# SC20.net
KiCad netlist of a schematic drawn in Altium Designer
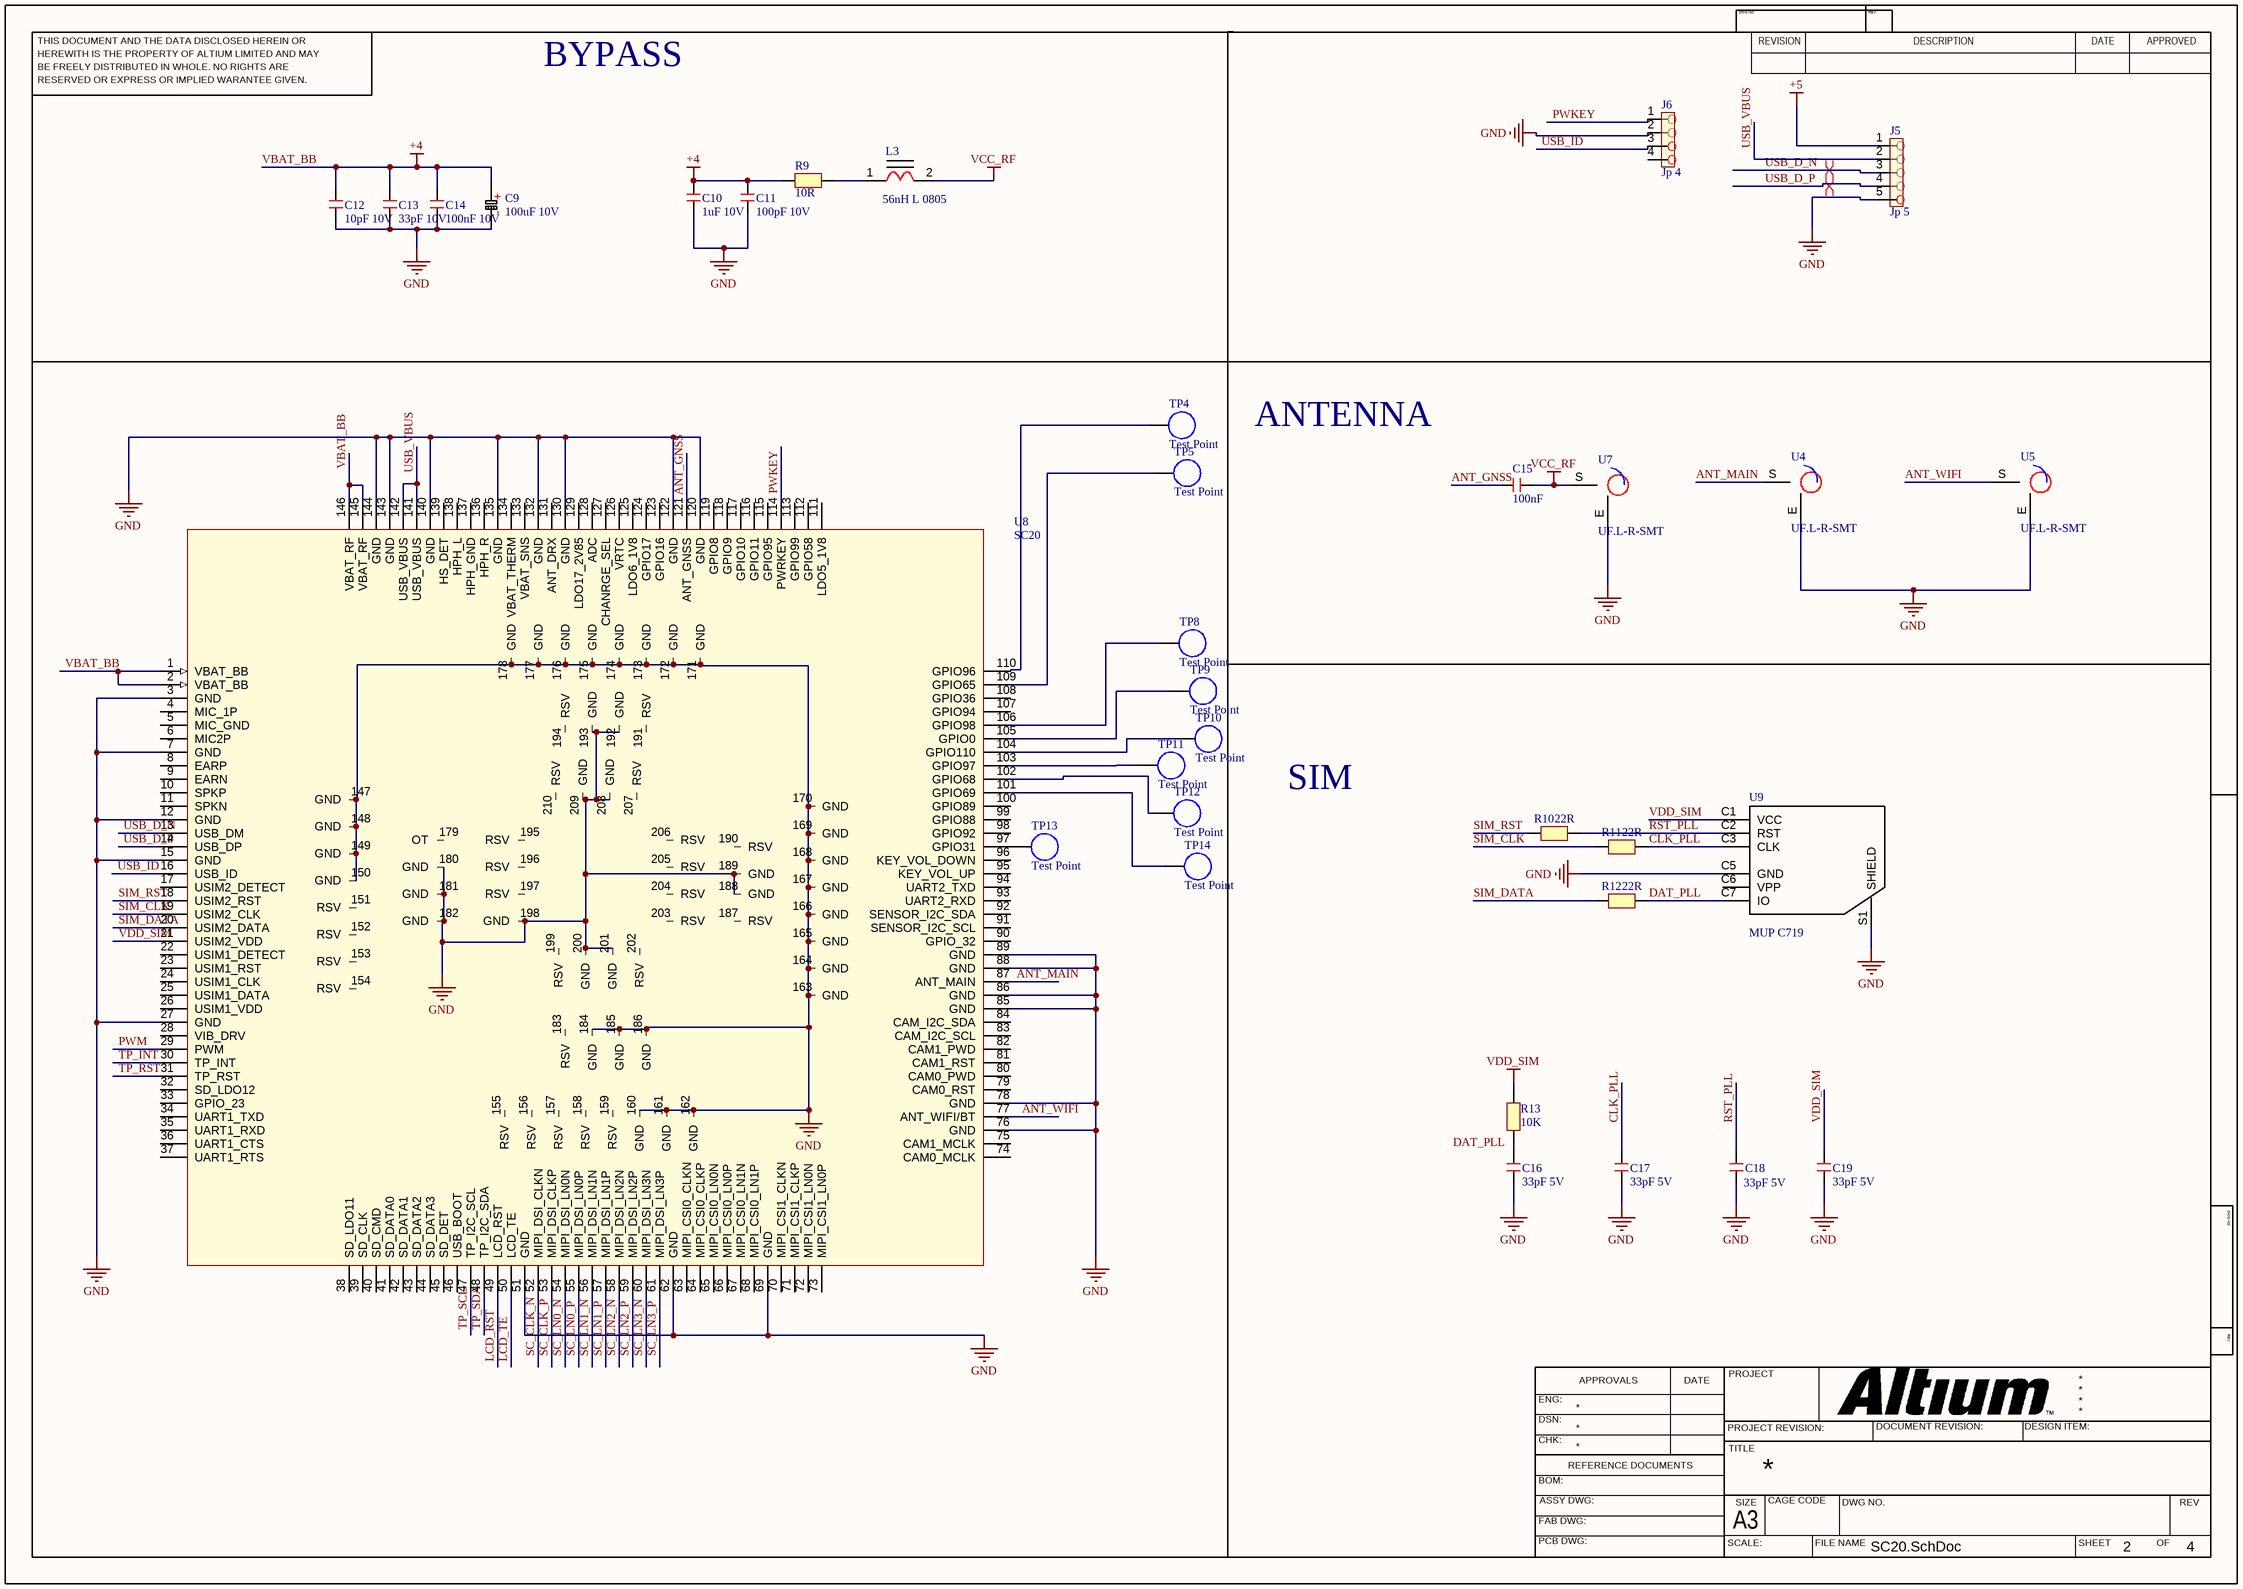
[diagram p0: SC20.SchDoc]

(export (version "E")
  (design (tool "Eeschema 10.0.6"))
  (components
    (comp (ref "C9")
      (value "100uF 10V")
      (footprint "CAPACITOR TALTALIUM 7443")
      (libsource (lib "NAVISTAR") (part "C Polarize 8x10.2"))
    )
    (comp (ref "C10") (value "1uF 10V") (footprint "C 0805") (libsource (lib "MAX2769_GPS") (part "C 0805")))
    (comp (ref "C11")
      (value "100pF 10V")
      (footprint "C 0805")
      (libsource (lib "MAX2769_GPS") (part "C 0805"))
    )
    (comp (ref "C12") (value "10pF 10V") (footprint "C 0805") (libsource (lib "MAX2769_GPS") (part "C 0805")))
    (comp (ref "C13") (value "33pF 10V") (footprint "C 0805") (libsource (lib "MAX2769_GPS") (part "C 0805")))
    (comp (ref "C14")
      (value "100nF 10V")
      (footprint "C 0805")
      (libsource (lib "MAX2769_GPS") (part "C 0805"))
    )
    (comp (ref "C15") (value "100nF") (footprint "C 0805") (libsource (lib "MAX2769_GPS") (part "C 0805")))
    (comp (ref "C16") (value "33pF 5V") (footprint "C 0805") (libsource (lib "MAX2769_GPS") (part "C 0805")))
    (comp (ref "C17") (value "33pF 5V") (footprint "C 0805") (libsource (lib "MAX2769_GPS") (part "C 0805")))
    (comp (ref "C18") (value "33pF 5V") (footprint "C 0805") (libsource (lib "MAX2769_GPS") (part "C 0805")))
    (comp (ref "C19") (value "33pF 5V") (footprint "C 0805") (libsource (lib "MAX2769_GPS") (part "C 0805")))
    (comp (ref "J5") (value "Jp 5") (footprint "Jp5") (libsource (lib "NAVISTAR") (part "Jp 5")))
    (comp (ref "J6") (value "Jp 4") (footprint "Jp4") (libsource (lib "NAVISTAR") (part "Jp 4")))
    (comp (ref "L3")
      (value "56nH L 0805")
      (footprint "Ferrite 0805")
      (libsource (lib "NAVISTAR") (part "Ferite 0805"))
    )
    (comp (ref "R9") (value "10R") (footprint "R 0805") (libsource (lib "") (part "R 0805_1")))
    (comp (ref "R10") (value "22R") (footprint "R 0805") (libsource (lib "") (part "R 0805_2")))
    (comp (ref "R11") (value "22R") (footprint "R 0805") (libsource (lib "") (part "R 0805_2")))
    (comp (ref "R12") (value "22R") (footprint "R 0805") (libsource (lib "") (part "R 0805_2")))
    (comp (ref "R13") (value "10K") (footprint "R 0805") (libsource (lib "MAX2769_GPS") (part "R 0805")))
    (comp (ref "TP4")
      (value "Test Point")
      (footprint "Test Point")
      (libsource (lib "NAVISTAR") (part "Test Point"))
    )
    (comp (ref "TP5")
      (value "Test Point")
      (footprint "Test Point")
      (libsource (lib "NAVISTAR") (part "Test Point"))
    )
    (comp (ref "TP8")
      (value "Test Point")
      (footprint "Test Point")
      (libsource (lib "NAVISTAR") (part "Test Point"))
    )
    (comp (ref "TP9")
      (value "Test Point")
      (footprint "Test Point")
      (libsource (lib "NAVISTAR") (part "Test Point"))
    )
    (comp (ref "TP10")
      (value "Test Point")
      (footprint "Test Point")
      (libsource (lib "NAVISTAR") (part "Test Point"))
    )
    (comp (ref "TP11")
      (value "Test Point")
      (footprint "Test Point")
      (libsource (lib "NAVISTAR") (part "Test Point"))
    )
    (comp (ref "TP12")
      (value "Test Point")
      (footprint "Test Point")
      (libsource (lib "NAVISTAR") (part "Test Point"))
    )
    (comp (ref "TP13")
      (value "Test Point")
      (footprint "Test Point")
      (libsource (lib "NAVISTAR") (part "Test Point"))
    )
    (comp (ref "TP14")
      (value "Test Point")
      (footprint "Test Point")
      (libsource (lib "NAVISTAR") (part "Test Point"))
    )
    (comp (ref "U4")
      (value "UF.L-R-SMT")
      (footprint "UFL")
      (libsource (lib "NAVISTAR_SoC") (part "UF.L-R-SMT"))
    )
    (comp (ref "U5")
      (value "UF.L-R-SMT")
      (footprint "UFL")
      (libsource (lib "NAVISTAR_SoC") (part "UF.L-R-SMT"))
    )
    (comp (ref "U7")
      (value "UF.L-R-SMT")
      (footprint "UFL")
      (libsource (lib "NAVISTAR_SoC") (part "UF.L-R-SMT"))
    )
    (comp (ref "U8") (value "SC20") (footprint "SC20") (libsource (lib "NAVISTAR_SoC") (part "SC20")))
    (comp (ref "U9") (value "MUP C719") (footprint "MPU C719") (libsource (lib "NAVISTAR") (part "MUP C719")))
  )
  (nets
    (net (code "1") (name "+4") (class "Default")
      (node (ref "C10") (pin "2") (pintype "passive"))
      (node (ref "C11") (pin "2") (pintype "passive"))
      (node (ref "C12") (pin "2") (pintype "passive"))
      (node (ref "C13") (pin "2") (pintype "passive"))
      (node (ref "C14") (pin "2") (pintype "passive"))
      (node (ref "C9") (pin "1") (pintype "passive"))
      (node (ref "R9") (pin "2") (pintype "passive"))
      (node (ref "U8") (pin "1") (pinfunction "VBAT_BB_1") (pintype "input"))
      (node (ref "U8") (pin "145") (pinfunction "VBAT_RF_145") (pintype "passive"))
      (node (ref "U8") (pin "146") (pinfunction "VBAT_RF_146") (pintype "passive"))
      (node (ref "U8") (pin "2") (pinfunction "VBAT_BB_2") (pintype "input"))
    )
    (net (code "2") (name "+5") (class "Default") (node (ref "J5") (pin "1") (pintype "passive")))
    (net (code "3") (name "/ANT_GNSS") (class "Default")
      (node (ref "C15") (pin "2") (pintype "passive"))
      (node (ref "U8") (pin "121") (pinfunction "ANT_GNSS_121") (pintype "passive"))
    )
    (net (code "4") (name "/ANT_MAIN") (class "Default")
      (node (ref "U4") (pin "S") (pintype "passive"))
      (node (ref "U8") (pin "87") (pinfunction "ANT_MAIN_87") (pintype "passive"))
    )
    (net (code "5") (name "/ANT_WIFI") (class "Default")
      (node (ref "U5") (pin "S") (pintype "passive"))
      (node (ref "U8") (pin "77") (pinfunction "ANT_WIFI/BT_77") (pintype "passive"))
    )
    (net (code "6") (name "/CLK_PLL") (class "Default")
      (node (ref "C17") (pin "2") (pintype "passive"))
      (node (ref "R11") (pin "2") (pintype "passive"))
      (node (ref "U9") (pin "C3") (pinfunction "CLK_C3") (pintype "passive"))
    )
    (net (code "7") (name "/DAT_PLL") (class "Default")
      (node (ref "R12") (pin "2") (pintype "passive"))
      (node (ref "U9") (pin "C7") (pinfunction "IO_C7") (pintype "passive"))
    )
    (net (code "8") (name "/LCD_RST") (class "Default")
      (node (ref "U8") (pin "49") (pinfunction "LCD_RST_49") (pintype "passive"))
    )
    (net (code "9") (name "/LCD_TE") (class "Default")
      (node (ref "U8") (pin "50") (pinfunction "LCD_TE_50") (pintype "passive"))
    )
    (net (code "10") (name "/PWKEY") (class "Default")
      (node (ref "J6") (pin "1") (pintype "passive"))
      (node (ref "U8") (pin "114") (pinfunction "PWRKEY_114") (pintype "passive"))
    )
    (net (code "11") (name "/PWM") (class "Default")
      (node (ref "U8") (pin "29") (pinfunction "PWM_29") (pintype "passive"))
    )
    (net (code "12") (name "/RST_PLL") (class "Default")
      (node (ref "C18") (pin "2") (pintype "passive"))
      (node (ref "R10") (pin "2") (pintype "passive"))
      (node (ref "U9") (pin "C2") (pinfunction "RST_C2") (pintype "passive"))
    )
    (net (code "13") (name "/SC_CLK_N") (class "Default")
      (node (ref "U8") (pin "52") (pinfunction "MIPI_DSI_CLKN_52") (pintype "passive"))
    )
    (net (code "14") (name "/SC_CLK_P") (class "Default")
      (node (ref "U8") (pin "53") (pinfunction "MIPI_DSI_CLKP_53") (pintype "passive"))
    )
    (net (code "15") (name "/SC_LN0_N") (class "Default")
      (node (ref "U8") (pin "54") (pinfunction "MIPI_DSI_LN0N_54") (pintype "passive"))
    )
    (net (code "16") (name "/SC_LN0_P") (class "Default")
      (node (ref "U8") (pin "55") (pinfunction "MIPI_DSI_LN0P_55") (pintype "passive"))
    )
    (net (code "17") (name "/SC_LN1_N") (class "Default")
      (node (ref "U8") (pin "56") (pinfunction "MIPI_DSI_LN1N_56") (pintype "passive"))
    )
    (net (code "18") (name "/SC_LN1_P") (class "Default")
      (node (ref "U8") (pin "57") (pinfunction "MIPI_DSI_LN1P_57") (pintype "passive"))
    )
    (net (code "19") (name "/SC_LN2_N") (class "Default")
      (node (ref "U8") (pin "58") (pinfunction "MIPI_DSI_LN2N_58") (pintype "passive"))
    )
    (net (code "20") (name "/SC_LN2_P") (class "Default")
      (node (ref "U8") (pin "59") (pinfunction "MIPI_DSI_LN2P_59") (pintype "passive"))
    )
    (net (code "21") (name "/SC_LN3_N") (class "Default")
      (node (ref "U8") (pin "60") (pinfunction "MIPI_DSI_LN3N_60") (pintype "passive"))
    )
    (net (code "22") (name "/SC_LN3_P") (class "Default")
      (node (ref "U8") (pin "61") (pinfunction "MIPI_DSI_LN3P_61") (pintype "passive"))
    )
    (net (code "23") (name "/SIM_CLK") (class "Default")
      (node (ref "R11") (pin "1") (pintype "passive"))
      (node (ref "U8") (pin "19") (pinfunction "USIM2_CLK_19") (pintype "passive"))
    )
    (net (code "24") (name "/SIM_DATA") (class "Default")
      (node (ref "R12") (pin "1") (pintype "passive"))
      (node (ref "U8") (pin "20") (pinfunction "USIM2_DATA_20") (pintype "passive"))
    )
    (net (code "25") (name "/SIM_RST") (class "Default")
      (node (ref "R10") (pin "1") (pintype "passive"))
      (node (ref "U8") (pin "18") (pinfunction "USIM2_RST_18") (pintype "passive"))
    )
    (net (code "26") (name "/TP_INT") (class "Default")
      (node (ref "U8") (pin "30") (pinfunction "TP_INT_30") (pintype "passive"))
    )
    (net (code "27") (name "/TP_RST") (class "Default")
      (node (ref "U8") (pin "31") (pinfunction "TP_RST_31") (pintype "passive"))
    )
    (net (code "28") (name "/TP_SCL") (class "Default")
      (node (ref "U8") (pin "47") (pinfunction "TP_I2C_SCL_47") (pintype "passive"))
    )
    (net (code "29") (name "/TP_SDA") (class "Default")
      (node (ref "U8") (pin "48") (pinfunction "TP_I2C_SDA_48") (pintype "passive"))
    )
    (net (code "30") (name "/USB_D_N") (class "Default")
      (node (ref "J5") (pin "3") (pintype "passive"))
      (node (ref "U8") (pin "13") (pinfunction "USB_DM_13") (pintype "passive"))
    )
    (net (code "31") (name "/USB_D_P") (class "Default")
      (node (ref "J5") (pin "4") (pintype "passive"))
      (node (ref "U8") (pin "14") (pinfunction "USB_DP_14") (pintype "passive"))
    )
    (net (code "32") (name "/USB_ID") (class "Default")
      (node (ref "J6") (pin "3") (pintype "passive"))
      (node (ref "U8") (pin "16") (pinfunction "USB_ID_16") (pintype "passive"))
    )
    (net (code "33") (name "/USB_VBUS") (class "Default")
      (node (ref "J5") (pin "2") (pintype "passive"))
      (node (ref "U8") (pin "141") (pinfunction "USB_VBUS_141") (pintype "passive"))
      (node (ref "U8") (pin "142") (pinfunction "USB_VBUS_142") (pintype "passive"))
    )
    (net (code "34") (name "GND") (class "Default")
      (node (ref "C10") (pin "1") (pintype "passive"))
      (node (ref "C11") (pin "1") (pintype "passive"))
      (node (ref "C12") (pin "1") (pintype "passive"))
      (node (ref "C13") (pin "1") (pintype "passive"))
      (node (ref "C14") (pin "1") (pintype "passive"))
      (node (ref "C16") (pin "1") (pintype "passive"))
      (node (ref "C17") (pin "1") (pintype "passive"))
      (node (ref "C18") (pin "1") (pintype "passive"))
      (node (ref "C19") (pin "1") (pintype "passive"))
      (node (ref "C9") (pin "2") (pintype "passive"))
      (node (ref "J5") (pin "5") (pintype "passive"))
      (node (ref "J6") (pin "2") (pintype "passive"))
      (node (ref "U4") (pin "E") (pintype "passive"))
      (node (ref "U5") (pin "E") (pintype "passive"))
      (node (ref "U7") (pin "E") (pintype "passive"))
      (node (ref "U8") (pin "12") (pinfunction "GND_12") (pintype "passive"))
      (node (ref "U8") (pin "120") (pinfunction "GND_120") (pintype "passive"))
      (node (ref "U8") (pin "122") (pinfunction "GND_122") (pintype "passive"))
      (node (ref "U8") (pin "130") (pinfunction "GND_130") (pintype "passive"))
      (node (ref "U8") (pin "132") (pinfunction "GND_132") (pintype "passive"))
      (node (ref "U8") (pin "135") (pinfunction "GND_135") (pintype "passive"))
      (node (ref "U8") (pin "140") (pinfunction "GND_140") (pintype "passive"))
      (node (ref "U8") (pin "143") (pinfunction "GND_143") (pintype "passive"))
      (node (ref "U8") (pin "144") (pinfunction "GND_144") (pintype "passive"))
      (node (ref "U8") (pin "147") (pinfunction "GND_147") (pintype "passive"))
      (node (ref "U8") (pin "148") (pinfunction "GND_148") (pintype "passive"))
      (node (ref "U8") (pin "149") (pinfunction "GND_149") (pintype "passive"))
      (node (ref "U8") (pin "15") (pinfunction "GND_15") (pintype "passive"))
      (node (ref "U8") (pin "150") (pinfunction "GND_150") (pintype "passive"))
      (node (ref "U8") (pin "160") (pinfunction "GND_160") (pintype "passive"))
      (node (ref "U8") (pin "161") (pinfunction "GND_161") (pintype "passive"))
      (node (ref "U8") (pin "162") (pinfunction "GND_162") (pintype "passive"))
      (node (ref "U8") (pin "163") (pinfunction "GND_163") (pintype "passive"))
      (node (ref "U8") (pin "164") (pinfunction "GND_164") (pintype "passive"))
      (node (ref "U8") (pin "165") (pinfunction "GND_165") (pintype "passive"))
      (node (ref "U8") (pin "166") (pinfunction "GND_166") (pintype "passive"))
      (node (ref "U8") (pin "167") (pinfunction "GND_167") (pintype "passive"))
      (node (ref "U8") (pin "168") (pinfunction "GND_168") (pintype "passive"))
      (node (ref "U8") (pin "169") (pinfunction "GND_169") (pintype "passive"))
      (node (ref "U8") (pin "170") (pinfunction "GND_170") (pintype "passive"))
      (node (ref "U8") (pin "171") (pinfunction "GND_171") (pintype "passive"))
      (node (ref "U8") (pin "172") (pinfunction "GND_172") (pintype "passive"))
      (node (ref "U8") (pin "173") (pinfunction "GND_173") (pintype "passive"))
      (node (ref "U8") (pin "174") (pinfunction "GND_174") (pintype "passive"))
      (node (ref "U8") (pin "175") (pinfunction "GND_175") (pintype "passive"))
      (node (ref "U8") (pin "176") (pinfunction "GND_176") (pintype "passive"))
      (node (ref "U8") (pin "177") (pinfunction "GND_177") (pintype "passive"))
      (node (ref "U8") (pin "178") (pinfunction "GND_178") (pintype "passive"))
      (node (ref "U8") (pin "180") (pinfunction "GND_180") (pintype "passive"))
      (node (ref "U8") (pin "181") (pinfunction "GND_181") (pintype "passive"))
      (node (ref "U8") (pin "182") (pinfunction "GND_182") (pintype "passive"))
      (node (ref "U8") (pin "184") (pinfunction "GND_184") (pintype "passive"))
      (node (ref "U8") (pin "185") (pinfunction "GND_185") (pintype "passive"))
      (node (ref "U8") (pin "186") (pinfunction "GND_186") (pintype "passive"))
      (node (ref "U8") (pin "188") (pinfunction "GND_188") (pintype "passive"))
      (node (ref "U8") (pin "189") (pinfunction "GND_189") (pintype "passive"))
      (node (ref "U8") (pin "192") (pinfunction "GND_192") (pintype "passive"))
      (node (ref "U8") (pin "193") (pinfunction "GND_193") (pintype "passive"))
      (node (ref "U8") (pin "198") (pinfunction "GND_198") (pintype "passive"))
      (node (ref "U8") (pin "200") (pinfunction "GND_200") (pintype "passive"))
      (node (ref "U8") (pin "201") (pinfunction "GND_201") (pintype "passive"))
      (node (ref "U8") (pin "208") (pinfunction "GND_208") (pintype "passive"))
      (node (ref "U8") (pin "209") (pinfunction "GND_209") (pintype "passive"))
      (node (ref "U8") (pin "27") (pinfunction "GND_27") (pintype "passive"))
      (node (ref "U8") (pin "3") (pinfunction "GND_3") (pintype "passive"))
      (node (ref "U8") (pin "51") (pinfunction "GND_51") (pintype "passive"))
      (node (ref "U8") (pin "62") (pinfunction "GND_62") (pintype "passive"))
      (node (ref "U8") (pin "69") (pinfunction "GND_69") (pintype "passive"))
      (node (ref "U8") (pin "7") (pinfunction "GND_7") (pintype "passive"))
      (node (ref "U8") (pin "76") (pinfunction "GND_76") (pintype "passive"))
      (node (ref "U8") (pin "78") (pinfunction "GND_78") (pintype "passive"))
      (node (ref "U8") (pin "85") (pinfunction "GND_85") (pintype "passive"))
      (node (ref "U8") (pin "86") (pinfunction "GND_86") (pintype "passive"))
      (node (ref "U8") (pin "88") (pinfunction "GND_88") (pintype "passive"))
      (node (ref "U8") (pin "89") (pinfunction "GND_89") (pintype "passive"))
      (node (ref "U9") (pin "C5") (pinfunction "GND_C5") (pintype "passive"))
      (node (ref "U9") (pin "S1") (pinfunction "SHIELD_S1") (pintype "passive"))
    )
    (net (code "35") (name "Net-(C16-Pad2)") (class "Default")
      (node (ref "C16") (pin "2") (pintype "passive"))
      (node (ref "R13") (pin "1") (pintype "passive"))
    )
    (net (code "36") (name "Net-(L3-Pad1)") (class "Default")
      (node (ref "L3") (pin "1") (pintype "passive"))
      (node (ref "R9") (pin "1") (pintype "passive"))
    )
    (net (code "37") (name "Net-(U8-GPIO0)") (class "Default")
      (node (ref "TP9") (pin "1") (pintype "passive"))
      (node (ref "U8") (pin "105") (pinfunction "GPIO0_105") (pintype "passive"))
    )
    (net (code "38") (name "Net-(U8-GPIO31)") (class "Default")
      (node (ref "TP13") (pin "1") (pintype "passive"))
      (node (ref "U8") (pin "97") (pinfunction "GPIO31_97") (pintype "passive"))
    )
    (net (code "39") (name "Net-(U8-GPIO65)") (class "Default")
      (node (ref "TP5") (pin "1") (pintype "passive"))
      (node (ref "U8") (pin "109") (pinfunction "GPIO65_109") (pintype "passive"))
    )
    (net (code "40") (name "Net-(U8-GPIO68)") (class "Default")
      (node (ref "TP12") (pin "1") (pintype "passive"))
      (node (ref "U8") (pin "102") (pinfunction "GPIO68_102") (pintype "passive"))
    )
    (net (code "41") (name "Net-(U8-GPIO69)") (class "Default")
      (node (ref "TP14") (pin "1") (pintype "passive"))
      (node (ref "U8") (pin "101") (pinfunction "GPIO69_101") (pintype "passive"))
    )
    (net (code "42") (name "Net-(U8-GPIO96)") (class "Default")
      (node (ref "TP4") (pin "1") (pintype "passive"))
      (node (ref "U8") (pin "110") (pinfunction "GPIO96_110") (pintype "passive"))
    )
    (net (code "43") (name "Net-(U8-GPIO97)") (class "Default")
      (node (ref "TP11") (pin "1") (pintype "passive"))
      (node (ref "U8") (pin "103") (pinfunction "GPIO97_103") (pintype "passive"))
    )
    (net (code "44") (name "Net-(U8-GPIO98)") (class "Default")
      (node (ref "TP8") (pin "1") (pintype "passive"))
      (node (ref "U8") (pin "106") (pinfunction "GPIO98_106") (pintype "passive"))
    )
    (net (code "45") (name "Net-(U8-GPIO110)") (class "Default")
      (node (ref "TP10") (pin "1") (pintype "passive"))
      (node (ref "U8") (pin "104") (pinfunction "GPIO110_104") (pintype "passive"))
    )
    (net (code "46") (name "VCC_RF") (class "Default")
      (node (ref "C15") (pin "1") (pintype "passive"))
      (node (ref "L3") (pin "2") (pintype "passive"))
      (node (ref "U7") (pin "S") (pintype "passive"))
    )
    (net (code "47") (name "VDD_SIM") (class "Default")
      (node (ref "C19") (pin "2") (pintype "passive"))
      (node (ref "R13") (pin "2") (pintype "passive"))
      (node (ref "U8") (pin "21") (pinfunction "USIM2_VDD_21") (pintype "passive"))
      (node (ref "U9") (pin "C1") (pinfunction "VCC_C1") (pintype "passive"))
    )
    (net (code "48") (name "unconnected-(J6-Pad4)") (class "Default")
      (node (ref "J6") (pin "4") (pintype "passive"))
    )
    (net (code "49") (name "unconnected-(U8-ADC-Pad128)") (class "Default")
      (node (ref "U8") (pin "128") (pinfunction "ADC_128") (pintype "passive"))
    )
    (net (code "50") (name "unconnected-(U8-ANT_DRX-Pad131)") (class "Default")
      (node (ref "U8") (pin "131") (pinfunction "ANT_DRX_131") (pintype "passive"))
    )
    (net (code "51") (name "unconnected-(U8-CAM0_MCLK-Pad74)") (class "Default")
      (node (ref "U8") (pin "74") (pinfunction "CAM0_MCLK_74") (pintype "passive"))
    )
    (net (code "52") (name "unconnected-(U8-CAM0_PWD-Pad80)") (class "Default")
      (node (ref "U8") (pin "80") (pinfunction "CAM0_PWD_80") (pintype "passive"))
    )
    (net (code "53") (name "unconnected-(U8-CAM0_RST-Pad79)") (class "Default")
      (node (ref "U8") (pin "79") (pinfunction "CAM0_RST_79") (pintype "passive"))
    )
    (net (code "54") (name "unconnected-(U8-CAM1_MCLK-Pad75)") (class "Default")
      (node (ref "U8") (pin "75") (pinfunction "CAM1_MCLK_75") (pintype "passive"))
    )
    (net (code "55") (name "unconnected-(U8-CAM1_PWD-Pad82)") (class "Default")
      (node (ref "U8") (pin "82") (pinfunction "CAM1_PWD_82") (pintype "passive"))
    )
    (net (code "56") (name "unconnected-(U8-CAM1_RST-Pad81)") (class "Default")
      (node (ref "U8") (pin "81") (pinfunction "CAM1_RST_81") (pintype "passive"))
    )
    (net (code "57") (name "unconnected-(U8-CAM_I2C_SCL-Pad83)") (class "Default")
      (node (ref "U8") (pin "83") (pinfunction "CAM_I2C_SCL_83") (pintype "passive"))
    )
    (net (code "58") (name "unconnected-(U8-CAM_I2C_SDA-Pad84)") (class "Default")
      (node (ref "U8") (pin "84") (pinfunction "CAM_I2C_SDA_84") (pintype "passive"))
    )
    (net (code "59") (name "unconnected-(U8-CHANRGE_SEL-Pad127)") (class "Default")
      (node (ref "U8") (pin "127") (pinfunction "CHANRGE_SEL_127") (pintype "passive"))
    )
    (net (code "60") (name "unconnected-(U8-EARN-Pad9)") (class "Default")
      (node (ref "U8") (pin "9") (pinfunction "EARN_9") (pintype "passive"))
    )
    (net (code "61") (name "unconnected-(U8-EARP-Pad8)") (class "Default")
      (node (ref "U8") (pin "8") (pinfunction "EARP_8") (pintype "passive"))
    )
    (net (code "62") (name "unconnected-(U8-GPIO8-Pad119)") (class "Default")
      (node (ref "U8") (pin "119") (pinfunction "GPIO8_119") (pintype "passive"))
    )
    (net (code "63") (name "unconnected-(U8-GPIO9-Pad118)") (class "Default")
      (node (ref "U8") (pin "118") (pinfunction "GPIO9_118") (pintype "passive"))
    )
    (net (code "64") (name "unconnected-(U8-GPIO10-Pad117)") (class "Default")
      (node (ref "U8") (pin "117") (pinfunction "GPIO10_117") (pintype "passive"))
    )
    (net (code "65") (name "unconnected-(U8-GPIO11-Pad116)") (class "Default")
      (node (ref "U8") (pin "116") (pinfunction "GPIO11_116") (pintype "passive"))
    )
    (net (code "66") (name "unconnected-(U8-GPIO16-Pad123)") (class "Default")
      (node (ref "U8") (pin "123") (pinfunction "GPIO16_123") (pintype "passive"))
    )
    (net (code "67") (name "unconnected-(U8-GPIO17-Pad124)") (class "Default")
      (node (ref "U8") (pin "124") (pinfunction "GPIO17_124") (pintype "passive"))
    )
    (net (code "68") (name "unconnected-(U8-GPIO36-Pad108)") (class "Default")
      (node (ref "U8") (pin "108") (pinfunction "GPIO36_108") (pintype "passive"))
    )
    (net (code "69") (name "unconnected-(U8-GPIO58-Pad112)") (class "Default")
      (node (ref "U8") (pin "112") (pinfunction "GPIO58_112") (pintype "passive"))
    )
    (net (code "70") (name "unconnected-(U8-GPIO88-Pad99)") (class "Default")
      (node (ref "U8") (pin "99") (pinfunction "GPIO88_99") (pintype "passive"))
    )
    (net (code "71") (name "unconnected-(U8-GPIO89-Pad100)") (class "Default")
      (node (ref "U8") (pin "100") (pinfunction "GPIO89_100") (pintype "passive"))
    )
    (net (code "72") (name "unconnected-(U8-GPIO92-Pad98)") (class "Default")
      (node (ref "U8") (pin "98") (pinfunction "GPIO92_98") (pintype "passive"))
    )
    (net (code "73") (name "unconnected-(U8-GPIO94-Pad107)") (class "Default")
      (node (ref "U8") (pin "107") (pinfunction "GPIO94_107") (pintype "passive"))
    )
    (net (code "74") (name "unconnected-(U8-GPIO95-Pad115)") (class "Default")
      (node (ref "U8") (pin "115") (pinfunction "GPIO95_115") (pintype "passive"))
    )
    (net (code "75") (name "unconnected-(U8-GPIO99-Pad113)") (class "Default")
      (node (ref "U8") (pin "113") (pinfunction "GPIO99_113") (pintype "passive"))
    )
    (net (code "76") (name "unconnected-(U8-GPIO_23-Pad33)") (class "Default")
      (node (ref "U8") (pin "33") (pinfunction "GPIO_23_33") (pintype "passive"))
    )
    (net (code "77") (name "unconnected-(U8-GPIO_32-Pad90)") (class "Default")
      (node (ref "U8") (pin "90") (pinfunction "GPIO_32_90") (pintype "passive"))
    )
    (net (code "78") (name "unconnected-(U8-HPH_GND-Pad137)") (class "Default")
      (node (ref "U8") (pin "137") (pinfunction "HPH_GND_137") (pintype "passive"))
    )
    (net (code "79") (name "unconnected-(U8-HPH_L-Pad138)") (class "Default")
      (node (ref "U8") (pin "138") (pinfunction "HPH_L_138") (pintype "passive"))
    )
    (net (code "80") (name "unconnected-(U8-HPH_R-Pad136)") (class "Default")
      (node (ref "U8") (pin "136") (pinfunction "HPH_R_136") (pintype "passive"))
    )
    (net (code "81") (name "unconnected-(U8-HS_DET-Pad139)") (class "Default")
      (node (ref "U8") (pin "139") (pinfunction "HS_DET_139") (pintype "passive"))
    )
    (net (code "82") (name "unconnected-(U8-KEY_VOL_DOWN-Pad96)") (class "Default")
      (node (ref "U8") (pin "96") (pinfunction "KEY_VOL_DOWN_96") (pintype "passive"))
    )
    (net (code "83") (name "unconnected-(U8-KEY_VOL_UP-Pad95)") (class "Default")
      (node (ref "U8") (pin "95") (pinfunction "KEY_VOL_UP_95") (pintype "passive"))
    )
    (net (code "84") (name "unconnected-(U8-LDO5_1V8-Pad111)") (class "Default")
      (node (ref "U8") (pin "111") (pinfunction "LDO5_1V8_111") (pintype "passive"))
    )
    (net (code "85") (name "unconnected-(U8-LDO6_1V8-Pad125)") (class "Default")
      (node (ref "U8") (pin "125") (pinfunction "LDO6_1V8_125") (pintype "passive"))
    )
    (net (code "86") (name "unconnected-(U8-LDO17_2V85-Pad129)") (class "Default")
      (node (ref "U8") (pin "129") (pinfunction "LDO17_2V85_129") (pintype "passive"))
    )
    (net (code "87") (name "unconnected-(U8-MIC2P-Pad6)") (class "Default")
      (node (ref "U8") (pin "6") (pinfunction "MIC2P_6") (pintype "passive"))
    )
    (net (code "88") (name "unconnected-(U8-MIC_1P-Pad4)") (class "Default")
      (node (ref "U8") (pin "4") (pinfunction "MIC_1P_4") (pintype "passive"))
    )
    (net (code "89") (name "unconnected-(U8-MIC_GND-Pad5)") (class "Default")
      (node (ref "U8") (pin "5") (pinfunction "MIC_GND_5") (pintype "passive"))
    )
    (net (code "90") (name "unconnected-(U8-MIPI_CSI0_CLKN-Pad63)") (class "Default")
      (node (ref "U8") (pin "63") (pinfunction "MIPI_CSI0_CLKN_63") (pintype "passive"))
    )
    (net (code "91") (name "unconnected-(U8-MIPI_CSI0_CLKP-Pad64)") (class "Default")
      (node (ref "U8") (pin "64") (pinfunction "MIPI_CSI0_CLKP_64") (pintype "passive"))
    )
    (net (code "92") (name "unconnected-(U8-MIPI_CSI0_LN0N-Pad65)") (class "Default")
      (node (ref "U8") (pin "65") (pinfunction "MIPI_CSI0_LN0N_65") (pintype "passive"))
    )
    (net (code "93") (name "unconnected-(U8-MIPI_CSI0_LN0P-Pad66)") (class "Default")
      (node (ref "U8") (pin "66") (pinfunction "MIPI_CSI0_LN0P_66") (pintype "passive"))
    )
    (net (code "94") (name "unconnected-(U8-MIPI_CSI0_LN1N-Pad67)") (class "Default")
      (node (ref "U8") (pin "67") (pinfunction "MIPI_CSI0_LN1N_67") (pintype "passive"))
    )
    (net (code "95") (name "unconnected-(U8-MIPI_CSI0_LN1P-Pad68)") (class "Default")
      (node (ref "U8") (pin "68") (pinfunction "MIPI_CSI0_LN1P_68") (pintype "passive"))
    )
    (net (code "96") (name "unconnected-(U8-MIPI_CSI1_CLKN-Pad70)") (class "Default")
      (node (ref "U8") (pin "70") (pinfunction "MIPI_CSI1_CLKN_70") (pintype "passive"))
    )
    (net (code "97") (name "unconnected-(U8-MIPI_CSI1_CLKP-Pad71)") (class "Default")
      (node (ref "U8") (pin "71") (pinfunction "MIPI_CSI1_CLKP_71") (pintype "passive"))
    )
    (net (code "98") (name "unconnected-(U8-MIPI_CSI1_LN0N-Pad72)") (class "Default")
      (node (ref "U8") (pin "72") (pinfunction "MIPI_CSI1_LN0N_72") (pintype "passive"))
    )
    (net (code "99") (name "unconnected-(U8-MIPI_CSI1_LN0P-Pad73)") (class "Default")
      (node (ref "U8") (pin "73") (pinfunction "MIPI_CSI1_LN0P_73") (pintype "passive"))
    )
    (net (code "100") (name "unconnected-(U8-OT-Pad179)") (class "Default")
      (node (ref "U8") (pin "179") (pinfunction "OT_179") (pintype "passive"))
    )
    (net (code "101") (name "unconnected-(U8-RSV-Pad151)") (class "Default")
      (node (ref "U8") (pin "151") (pinfunction "RSV_151") (pintype "passive"))
    )
    (net (code "102") (name "unconnected-(U8-RSV-Pad152)") (class "Default")
      (node (ref "U8") (pin "152") (pinfunction "RSV_152") (pintype "passive"))
    )
    (net (code "103") (name "unconnected-(U8-RSV-Pad153)") (class "Default")
      (node (ref "U8") (pin "153") (pinfunction "RSV_153") (pintype "passive"))
    )
    (net (code "104") (name "unconnected-(U8-RSV-Pad154)") (class "Default")
      (node (ref "U8") (pin "154") (pinfunction "RSV_154") (pintype "passive"))
    )
    (net (code "105") (name "unconnected-(U8-RSV-Pad155)") (class "Default")
      (node (ref "U8") (pin "155") (pinfunction "RSV_155") (pintype "passive"))
    )
    (net (code "106") (name "unconnected-(U8-RSV-Pad156)") (class "Default")
      (node (ref "U8") (pin "156") (pinfunction "RSV_156") (pintype "passive"))
    )
    (net (code "107") (name "unconnected-(U8-RSV-Pad157)") (class "Default")
      (node (ref "U8") (pin "157") (pinfunction "RSV_157") (pintype "passive"))
    )
    (net (code "108") (name "unconnected-(U8-RSV-Pad158)") (class "Default")
      (node (ref "U8") (pin "158") (pinfunction "RSV_158") (pintype "passive"))
    )
    (net (code "109") (name "unconnected-(U8-RSV-Pad159)") (class "Default")
      (node (ref "U8") (pin "159") (pinfunction "RSV_159") (pintype "passive"))
    )
    (net (code "110") (name "unconnected-(U8-RSV-Pad183)") (class "Default")
      (node (ref "U8") (pin "183") (pinfunction "RSV_183") (pintype "passive"))
    )
    (net (code "111") (name "unconnected-(U8-RSV-Pad187)") (class "Default")
      (node (ref "U8") (pin "187") (pinfunction "RSV_187") (pintype "passive"))
    )
    (net (code "112") (name "unconnected-(U8-RSV-Pad190)") (class "Default")
      (node (ref "U8") (pin "190") (pinfunction "RSV_190") (pintype "passive"))
    )
    (net (code "113") (name "unconnected-(U8-RSV-Pad191)") (class "Default")
      (node (ref "U8") (pin "191") (pinfunction "RSV_191") (pintype "passive"))
    )
    (net (code "114") (name "unconnected-(U8-RSV-Pad194)") (class "Default")
      (node (ref "U8") (pin "194") (pinfunction "RSV_194") (pintype "passive"))
    )
    (net (code "115") (name "unconnected-(U8-RSV-Pad195)") (class "Default")
      (node (ref "U8") (pin "195") (pinfunction "RSV_195") (pintype "passive"))
    )
    (net (code "116") (name "unconnected-(U8-RSV-Pad196)") (class "Default")
      (node (ref "U8") (pin "196") (pinfunction "RSV_196") (pintype "passive"))
    )
    (net (code "117") (name "unconnected-(U8-RSV-Pad197)") (class "Default")
      (node (ref "U8") (pin "197") (pinfunction "RSV_197") (pintype "passive"))
    )
    (net (code "118") (name "unconnected-(U8-RSV-Pad199)") (class "Default")
      (node (ref "U8") (pin "199") (pinfunction "RSV_199") (pintype "passive"))
    )
    (net (code "119") (name "unconnected-(U8-RSV-Pad202)") (class "Default")
      (node (ref "U8") (pin "202") (pinfunction "RSV_202") (pintype "passive"))
    )
    (net (code "120") (name "unconnected-(U8-RSV-Pad203)") (class "Default")
      (node (ref "U8") (pin "203") (pinfunction "RSV_203") (pintype "passive"))
    )
    (net (code "121") (name "unconnected-(U8-RSV-Pad204)") (class "Default")
      (node (ref "U8") (pin "204") (pinfunction "RSV_204") (pintype "passive"))
    )
    (net (code "122") (name "unconnected-(U8-RSV-Pad205)") (class "Default")
      (node (ref "U8") (pin "205") (pinfunction "RSV_205") (pintype "passive"))
    )
    (net (code "123") (name "unconnected-(U8-RSV-Pad206)") (class "Default")
      (node (ref "U8") (pin "206") (pinfunction "RSV_206") (pintype "passive"))
    )
    (net (code "124") (name "unconnected-(U8-RSV-Pad207)") (class "Default")
      (node (ref "U8") (pin "207") (pinfunction "RSV_207") (pintype "passive"))
    )
    (net (code "125") (name "unconnected-(U8-RSV-Pad210)") (class "Default")
      (node (ref "U8") (pin "210") (pinfunction "RSV_210") (pintype "passive"))
    )
    (net (code "126") (name "unconnected-(U8-SD_CLK-Pad39)") (class "Default")
      (node (ref "U8") (pin "39") (pinfunction "SD_CLK_39") (pintype "passive"))
    )
    (net (code "127") (name "unconnected-(U8-SD_CMD-Pad40)") (class "Default")
      (node (ref "U8") (pin "40") (pinfunction "SD_CMD_40") (pintype "passive"))
    )
    (net (code "128") (name "unconnected-(U8-SD_DATA0-Pad41)") (class "Default")
      (node (ref "U8") (pin "41") (pinfunction "SD_DATA0_41") (pintype "passive"))
    )
    (net (code "129") (name "unconnected-(U8-SD_DATA1-Pad42)") (class "Default")
      (node (ref "U8") (pin "42") (pinfunction "SD_DATA1_42") (pintype "passive"))
    )
    (net (code "130") (name "unconnected-(U8-SD_DATA2-Pad43)") (class "Default")
      (node (ref "U8") (pin "43") (pinfunction "SD_DATA2_43") (pintype "passive"))
    )
    (net (code "131") (name "unconnected-(U8-SD_DATA3-Pad44)") (class "Default")
      (node (ref "U8") (pin "44") (pinfunction "SD_DATA3_44") (pintype "passive"))
    )
    (net (code "132") (name "unconnected-(U8-SD_DET-Pad45)") (class "Default")
      (node (ref "U8") (pin "45") (pinfunction "SD_DET_45") (pintype "passive"))
    )
    (net (code "133") (name "unconnected-(U8-SD_LDO11-Pad38)") (class "Default")
      (node (ref "U8") (pin "38") (pinfunction "SD_LDO11_38") (pintype "passive"))
    )
    (net (code "134") (name "unconnected-(U8-SD_LDO12-Pad32)") (class "Default")
      (node (ref "U8") (pin "32") (pinfunction "SD_LDO12_32") (pintype "passive"))
    )
    (net (code "135") (name "unconnected-(U8-SENSOR_I2C_SCL-Pad91)") (class "Default")
      (node (ref "U8") (pin "91") (pinfunction "SENSOR_I2C_SCL_91") (pintype "passive"))
    )
    (net (code "136") (name "unconnected-(U8-SENSOR_I2C_SDA-Pad92)") (class "Default")
      (node (ref "U8") (pin "92") (pinfunction "SENSOR_I2C_SDA_92") (pintype "passive"))
    )
    (net (code "137") (name "unconnected-(U8-SPKN-Pad11)") (class "Default")
      (node (ref "U8") (pin "11") (pinfunction "SPKN_11") (pintype "passive"))
    )
    (net (code "138") (name "unconnected-(U8-SPKP-Pad10)") (class "Default")
      (node (ref "U8") (pin "10") (pinfunction "SPKP_10") (pintype "passive"))
    )
    (net (code "139") (name "unconnected-(U8-UART1_CTS-Pad36)") (class "Default")
      (node (ref "U8") (pin "36") (pinfunction "UART1_CTS_36") (pintype "passive"))
    )
    (net (code "140") (name "unconnected-(U8-UART1_RTS-Pad37)") (class "Default")
      (node (ref "U8") (pin "37") (pinfunction "UART1_RTS_37") (pintype "passive"))
    )
    (net (code "141") (name "unconnected-(U8-UART1_RXD-Pad35)") (class "Default")
      (node (ref "U8") (pin "35") (pinfunction "UART1_RXD_35") (pintype "passive"))
    )
    (net (code "142") (name "unconnected-(U8-UART1_TXD-Pad34)") (class "Default")
      (node (ref "U8") (pin "34") (pinfunction "UART1_TXD_34") (pintype "passive"))
    )
    (net (code "143") (name "unconnected-(U8-UART2_RXD-Pad93)") (class "Default")
      (node (ref "U8") (pin "93") (pinfunction "UART2_RXD_93") (pintype "passive"))
    )
    (net (code "144") (name "unconnected-(U8-UART2_TXD-Pad94)") (class "Default")
      (node (ref "U8") (pin "94") (pinfunction "UART2_TXD_94") (pintype "passive"))
    )
    (net (code "145") (name "unconnected-(U8-USB_BOOT-Pad46)") (class "Default")
      (node (ref "U8") (pin "46") (pinfunction "USB_BOOT_46") (pintype "passive"))
    )
    (net (code "146") (name "unconnected-(U8-USIM1_CLK-Pad24)") (class "Default")
      (node (ref "U8") (pin "24") (pinfunction "USIM1_CLK_24") (pintype "passive"))
    )
    (net (code "147") (name "unconnected-(U8-USIM1_DATA-Pad25)") (class "Default")
      (node (ref "U8") (pin "25") (pinfunction "USIM1_DATA_25") (pintype "passive"))
    )
    (net (code "148") (name "unconnected-(U8-USIM1_DETECT-Pad22)") (class "Default")
      (node (ref "U8") (pin "22") (pinfunction "USIM1_DETECT_22") (pintype "passive"))
    )
    (net (code "149") (name "unconnected-(U8-USIM1_RST-Pad23)") (class "Default")
      (node (ref "U8") (pin "23") (pinfunction "USIM1_RST_23") (pintype "passive"))
    )
    (net (code "150") (name "unconnected-(U8-USIM1_VDD-Pad26)") (class "Default")
      (node (ref "U8") (pin "26") (pinfunction "USIM1_VDD_26") (pintype "passive"))
    )
    (net (code "151") (name "unconnected-(U8-USIM2_DETECT-Pad17)") (class "Default")
      (node (ref "U8") (pin "17") (pinfunction "USIM2_DETECT_17") (pintype "passive"))
    )
    (net (code "152") (name "unconnected-(U8-VBAT_SNS-Pad133)") (class "Default")
      (node (ref "U8") (pin "133") (pinfunction "VBAT_SNS_133") (pintype "passive"))
    )
    (net (code "153") (name "unconnected-(U8-VBAT_THERM-Pad134)") (class "Default")
      (node (ref "U8") (pin "134") (pinfunction "VBAT_THERM_134") (pintype "passive"))
    )
    (net (code "154") (name "unconnected-(U8-VIB_DRV-Pad28)") (class "Default")
      (node (ref "U8") (pin "28") (pinfunction "VIB_DRV_28") (pintype "passive"))
    )
    (net (code "155") (name "unconnected-(U8-VRTC-Pad126)") (class "Default")
      (node (ref "U8") (pin "126") (pinfunction "VRTC_126") (pintype "passive"))
    )
    (net (code "156") (name "unconnected-(U9-VPP-PadC6)") (class "Default")
      (node (ref "U9") (pin "C6") (pinfunction "VPP_C6") (pintype "passive"))
    )
  )
)
